# Sheet2.net
KiCad netlist of a schematic drawn in Altium Designer
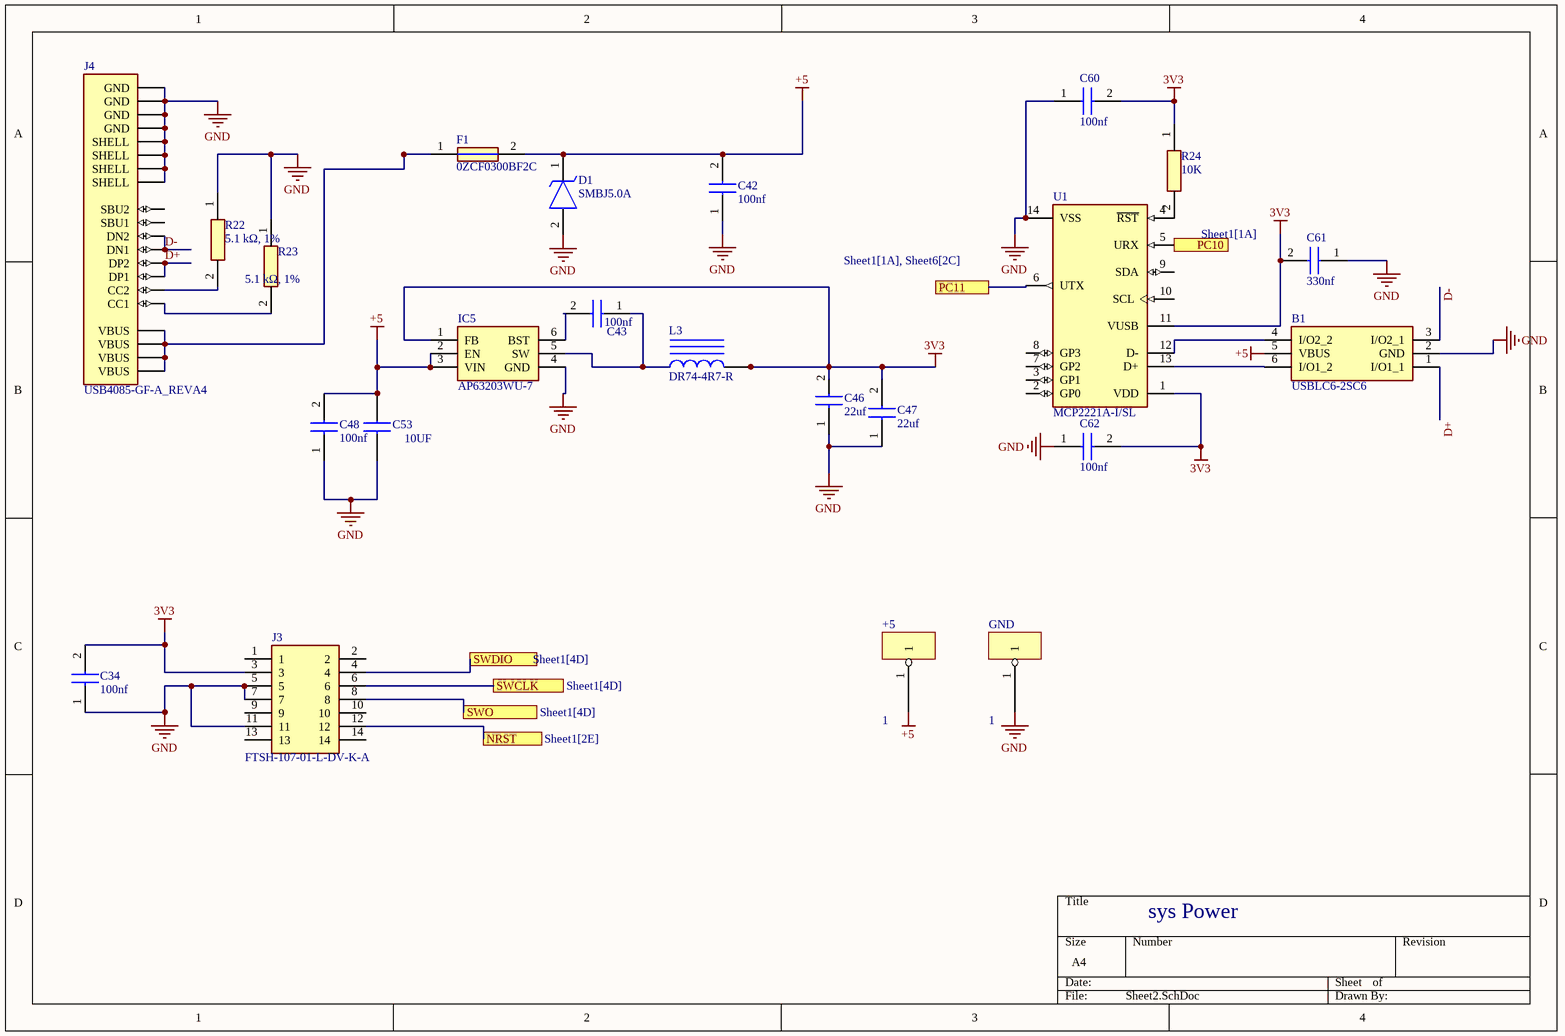
[diagram p0: Sheet2.SchDoc]

(export (version "E")
  (design (tool "Eeschema 10.0.6"))
  (components
    (comp (ref "+5") (value "1") (footprint "ANT") (libsource (lib "ANT") (part "1")))
    (comp (ref "B1")
      (value "USBLC6-2SC6")
      (footprint "SOT95P280X145-6N")
      (description "TVS Diode Array Uni-Directional USBLC6-2SC6 17V, SOT-23 6-Pin")
      (fields (field (name "MOUSER PART NUMBER") "511-USBLC6-2SC6"))
      (libsource (lib "USBLC6-2SC6") (part "USBLC6-2SC6"))
    )
    (comp (ref "C34")
      (value "100nf")
      (footprint "SamacSys:CAPC1608X95N")
      (description "Capacitor")
      (fields (field (name "MANUFACTURER_PART_NUMBER") "VJ0603Y104KXACW1BC"))
      (libsource (lib "*") (part "VJ0603Y104KXACW1BC"))
    )
    (comp (ref "C42")
      (value "100nf")
      (footprint "SamacSys:CAPC1608X95N")
      (description "Capacitor")
      (fields (field (name "MANUFACTURER_PART_NUMBER") "VJ0603Y104KXACW1BC"))
      (libsource (lib "*") (part "VJ0603Y104KXACW1BC"))
    )
    (comp (ref "C43")
      (value "100nf")
      (footprint "SamacSys:CAPC1608X95N")
      (description "Capacitor")
      (fields (field (name "MANUFACTURER_PART_NUMBER") "VJ0603Y104KXACW1BC"))
      (libsource (lib "*") (part "VJ0603Y104KXACW1BC"))
    )
    (comp (ref "C46")
      (value "22uf")
      (footprint "SamacSys:CAPC1608X95N")
      (description "Capacitor")
      (fields (field (name "MANUFACTURER_PART_NUMBER") "VJ0603Y104KXACW1BC"))
      (libsource (lib "*") (part "VJ0603Y104KXACW1BC"))
    )
    (comp (ref "C47")
      (value "22uf")
      (footprint "SamacSys:CAPC1608X95N")
      (description "Capacitor")
      (fields (field (name "MANUFACTURER_PART_NUMBER") "VJ0603Y104KXACW1BC"))
      (libsource (lib "*") (part "VJ0603Y104KXACW1BC"))
    )
    (comp (ref "C48")
      (value "100nf")
      (footprint "SamacSys:CAPC1608X95N")
      (description "Capacitor")
      (fields (field (name "MANUFACTURER_PART_NUMBER") "VJ0603Y104KXACW1BC"))
      (libsource (lib "*") (part "VJ0603Y104KXACW1BC"))
    )
    (comp (ref "C53")
      (value "10UF")
      (footprint "CAPC1608X90N")
      (description "10F +/-10% 10V Ceramic Capacitor X5R 0603 (1608 Metric)")
      (fields
        (field (name "MANUFACTURER_PART_NUMBER") "CL10A106KP8NNNC")
        (field (name "MOUSER PART NUMBER") "187-CL10A106KP8NNNC")
      )
      (libsource (lib "CL10A106KP8NNNC") (part "CL10A106KP8NNNC"))
    )
    (comp (ref "C60")
      (value "100nf")
      (footprint "SamacSys:CAPC1608X95N")
      (description "Capacitor")
      (fields (field (name "MANUFACTURER_PART_NUMBER") "VJ0603Y104KXACW1BC"))
      (libsource (lib "*") (part "VJ0603Y104KXACW1BC"))
    )
    (comp (ref "C61")
      (value "330nf")
      (footprint "SamacSys:CAPC1608X95N")
      (description "Capacitor")
      (fields (field (name "MANUFACTURER_PART_NUMBER") "VJ0603Y104KXACW1BC"))
      (libsource (lib "*") (part "VJ0603Y104KXACW1BC"))
    )
    (comp (ref "C62")
      (value "100nf")
      (footprint "SamacSys:CAPC1608X95N")
      (description "Capacitor")
      (fields (field (name "MANUFACTURER_PART_NUMBER") "VJ0603Y104KXACW1BC"))
      (libsource (lib "*") (part "VJ0603Y104KXACW1BC"))
    )
    (comp (ref "D1")
      (value "SMBJ5.0A")
      (footprint "SamacSys:SMBJ12A")
      (description "TVS Diode (Uni-directional)")
      (libsource (lib "SamacSys") (part "SMBJ5.0A"))
    )
    (comp (ref "F1")
      (value "0ZCF0300BF2C")
      (footprint "SamacSys:FUSC7451X115N")
      (description "Fuse")
      (fields (field (name "MOUSER PART NUMBER") "530-0ZCF0300BF2C"))
      (libsource (lib "*") (part "0ZCF0300BF2C"))
    )
    (comp (ref "GND") (value "1") (footprint "ANT") (libsource (lib "ANT") (part "1")))
    (comp (ref "IC5")
      (value "AP63203WU-7")
      (footprint "SamacSys:AP63203WU7")
      (description "Integrated Circuit")
      (fields (field (name "MOUSER PART NUMBER") "621-AP63203WU-7"))
      (libsource (lib "*") (part "AP63203WU-7"))
    )
    (comp (ref "J3")
      (value "FTSH-107-01-L-DV-K-A")
      (footprint "SamacSys:FTSH-107-XX-YYY-DV-K-A")
      (description "Connector")
      (fields (field (name "MOUSER PART NUMBER") "200-FTSH10701LDVKA"))
      (libsource (lib "*") (part "FTSH-107-01-L-DV-K-A"))
    )
    (comp (ref "J4")
      (value "USB4085-GF-A_REVA4")
      (footprint "GCT_USB4085-GF-A_REVA4")
      (fields (field (name "MP") "USB4085-GF-A") (field (name "MF") "Global Connector Technology"))
      (libsource (lib "USB4085-GF-A_REVA4") (part "USB4085-GF-A_REVA4"))
    )
    (comp (ref "L3")
      (value "DR74-4R7-R")
      (footprint "COBU-DR74-4R7-R_V")
      (fields (field (name "MANUFACTURER") "Eaton") (field (name "TOLERANCE") "±20%"))
      (libsource (lib "Altium Content Vault") (part "IND-DOT-2_A"))
    )
    (comp (ref "R22")
      (value "5.1 kΩ, 1%")
      (footprint "SamacSys:RESC1608X55N")
      (description "Resistor")
      (fields
        (field (name "MANUFACTURER_PART_NUMBER") "RC0603FR-071KL")
        (field (name "MOUSER PART NUMBER") "603-RC0603FR-071KL")
      )
      (libsource (lib "*") (part "RC0603FR-071KL"))
    )
    (comp (ref "R23")
      (value "5.1 kΩ, 1%")
      (footprint "SamacSys:RESC1608X55N")
      (description "Resistor")
      (fields
        (field (name "MANUFACTURER_PART_NUMBER") "RC0603FR-071KL")
        (field (name "MOUSER PART NUMBER") "603-RC0603FR-071KL")
      )
      (libsource (lib "*") (part "RC0603FR-071KL"))
    )
    (comp (ref "R24")
      (value "10K")
      (footprint "SamacSys:RESC1608X55N")
      (description "Resistor")
      (fields
        (field (name "MANUFACTURER_PART_NUMBER") "RC0603FR-071KL")
        (field (name "MOUSER PART NUMBER") "603-RC0603FR-071KL")
      )
      (libsource (lib "*") (part "RC0603FR-071KL"))
    )
    (comp (ref "U1")
      (value "MCP2221A-I/SL")
      (footprint "FP-C04-065-SL-MFG")
      (description "IC USB TO I2C/UART 14SOIC")
      (fields
        (field (name "OCTOPART") "https://octopart.com/mcp2221a-i%2Fsl-microchip-71704986")
        (field (name "MANUFACTURER") "Microchip")
      )
      (libsource (lib "Altium Content Vault") (part "1b53208594fde27bd45fc2fa1d78706"))
    )
  )
  (nets
    (net (code "1") (name "+5") (class "Default")
      (node (ref "+5") (pin "1") (pinfunction "1_1") (pintype "passive"))
      (node (ref "B1") (pin "5") (pinfunction "VBUS_5") (pintype "passive"))
      (node (ref "C42") (pin "2") (pinfunction "2_2") (pintype "passive"))
      (node (ref "C48") (pin "2") (pinfunction "2_2") (pintype "passive"))
      (node (ref "C53") (pin "2") (pinfunction "2_2") (pintype "passive"))
      (node (ref "D1") (pin "1") (pinfunction "K_1") (pintype "passive"))
      (node (ref "F1") (pin "2") (pinfunction "2_2") (pintype "passive"))
      (node (ref "IC5") (pin "2") (pinfunction "EN_2") (pintype "passive"))
      (node (ref "IC5") (pin "3") (pinfunction "VIN_3") (pintype "passive"))
    )
    (net (code "2") (name "/D+") (class "Default")
      (node (ref "B1") (pin "1") (pinfunction "I/O1_1_1") (pintype "passive"))
      (node (ref "J4") (pin "A6") (pinfunction "DP1_A6") (pintype "bidirectional"))
      (node (ref "J4") (pin "B6") (pinfunction "DP2_B6") (pintype "bidirectional"))
    )
    (net (code "3") (name "/D-") (class "Default")
      (node (ref "B1") (pin "3") (pinfunction "I/O2_1_3") (pintype "passive"))
      (node (ref "J4") (pin "A7") (pinfunction "DN1_A7") (pintype "bidirectional"))
      (node (ref "J4") (pin "B7") (pinfunction "DN2_B7") (pintype "bidirectional"))
    )
    (net (code "4") (name "/NRST") (class "Default")
      (node (ref "J3") (pin "12") (pinfunction "12_12") (pintype "passive"))
    )
    (net (code "5") (name "/PC10") (class "Default")
      (node (ref "U1") (pin "5") (pinfunction "URX_5") (pintype "input"))
    )
    (net (code "6") (name "/PC11") (class "Default")
      (node (ref "U1") (pin "6") (pinfunction "UTX_6") (pintype "output"))
    )
    (net (code "7") (name "/SWCLK") (class "Default")
      (node (ref "J3") (pin "6") (pinfunction "6_6") (pintype "passive"))
    )
    (net (code "8") (name "/SWDIO") (class "Default")
      (node (ref "J3") (pin "4") (pinfunction "4_4") (pintype "passive"))
    )
    (net (code "9") (name "/SWO") (class "Default")
      (node (ref "J3") (pin "8") (pinfunction "8_8") (pintype "passive"))
    )
    (net (code "10") (name "3V3") (class "Default")
      (node (ref "C34") (pin "2") (pinfunction "2_2") (pintype "passive"))
      (node (ref "C46") (pin "2") (pinfunction "2_2") (pintype "passive"))
      (node (ref "C47") (pin "2") (pinfunction "2_2") (pintype "passive"))
      (node (ref "C60") (pin "2") (pinfunction "2_2") (pintype "passive"))
      (node (ref "C61") (pin "2") (pinfunction "2_2") (pintype "passive"))
      (node (ref "C62") (pin "2") (pinfunction "2_2") (pintype "passive"))
      (node (ref "IC5") (pin "1") (pinfunction "FB_1") (pintype "passive"))
      (node (ref "J3") (pin "3") (pinfunction "3_3") (pintype "passive"))
      (node (ref "L3") (pin "2") (pinfunction "2_2") (pintype "passive"))
      (node (ref "R24") (pin "1") (pinfunction "1_1") (pintype "passive"))
      (node (ref "U1") (pin "1") (pinfunction "VDD_1") (pintype "power_in"))
      (node (ref "U1") (pin "11") (pinfunction "VUSB_11") (pintype "power_in"))
    )
    (net (code "11") (name "GND") (class "Default")
      (node (ref "B1") (pin "2") (pinfunction "GND_2") (pintype "passive"))
      (node (ref "C34") (pin "1") (pinfunction "1_1") (pintype "passive"))
      (node (ref "C42") (pin "1") (pinfunction "1_1") (pintype "passive"))
      (node (ref "C46") (pin "1") (pinfunction "1_1") (pintype "passive"))
      (node (ref "C47") (pin "1") (pinfunction "1_1") (pintype "passive"))
      (node (ref "C48") (pin "1") (pinfunction "1_1") (pintype "passive"))
      (node (ref "C53") (pin "1") (pinfunction "1_1") (pintype "passive"))
      (node (ref "C60") (pin "1") (pinfunction "1_1") (pintype "passive"))
      (node (ref "C61") (pin "1") (pinfunction "1_1") (pintype "passive"))
      (node (ref "C62") (pin "1") (pinfunction "1_1") (pintype "passive"))
      (node (ref "D1") (pin "2") (pinfunction "A_2") (pintype "passive"))
      (node (ref "GND") (pin "1") (pinfunction "1_1") (pintype "passive"))
      (node (ref "IC5") (pin "4") (pinfunction "GND_4") (pintype "passive"))
      (node (ref "J3") (pin "11") (pinfunction "11_11") (pintype "passive"))
      (node (ref "J3") (pin "5") (pinfunction "5_5") (pintype "passive"))
      (node (ref "J3") (pin "7") (pinfunction "7_7") (pintype "passive"))
      (node (ref "J4") (pin "A1") (pinfunction "GND_A1") (pintype "power_in"))
      (node (ref "J4") (pin "A12") (pinfunction "GND_A12") (pintype "power_in"))
      (node (ref "J4") (pin "B1") (pinfunction "GND_B1") (pintype "power_in"))
      (node (ref "J4") (pin "B12") (pinfunction "GND_B12") (pintype "power_in"))
      (node (ref "J4") (pin "S1") (pinfunction "SHELL_S1") (pintype "passive"))
      (node (ref "J4") (pin "S2") (pinfunction "SHELL_S2") (pintype "passive"))
      (node (ref "J4") (pin "S3") (pinfunction "SHELL_S3") (pintype "passive"))
      (node (ref "J4") (pin "S4") (pinfunction "SHELL_S4") (pintype "passive"))
      (node (ref "R22") (pin "1") (pinfunction "1_1") (pintype "passive"))
      (node (ref "R23") (pin "1") (pinfunction "1_1") (pintype "passive"))
      (node (ref "U1") (pin "14") (pinfunction "VSS_14") (pintype "power_in"))
    )
    (net (code "12") (name "Net-(B1-I{slash}O1_2)") (class "Default")
      (node (ref "B1") (pin "6") (pinfunction "I/O1_2_6") (pintype "passive"))
      (node (ref "U1") (pin "13") (pinfunction "D+_13") (pintype "power_in"))
    )
    (net (code "13") (name "Net-(B1-I{slash}O2_2)") (class "Default")
      (node (ref "B1") (pin "4") (pinfunction "I/O2_2_4") (pintype "passive"))
      (node (ref "U1") (pin "12") (pinfunction "D-_12") (pintype "power_in"))
    )
    (net (code "14") (name "Net-(F1-Pad1)") (class "Default")
      (node (ref "F1") (pin "1") (pinfunction "1_1") (pintype "passive"))
      (node (ref "J4") (pin "A4") (pinfunction "VBUS_A4") (pintype "power_in"))
      (node (ref "J4") (pin "A9") (pinfunction "VBUS_A9") (pintype "power_in"))
      (node (ref "J4") (pin "B4") (pinfunction "VBUS_B4") (pintype "power_in"))
      (node (ref "J4") (pin "B9") (pinfunction "VBUS_B9") (pintype "power_in"))
    )
    (net (code "15") (name "Net-(IC5-BST)") (class "Default")
      (node (ref "C43") (pin "2") (pinfunction "2_2") (pintype "passive"))
      (node (ref "IC5") (pin "6") (pinfunction "BST_6") (pintype "passive"))
    )
    (net (code "16") (name "Net-(IC5-SW)") (class "Default")
      (node (ref "C43") (pin "1") (pinfunction "1_1") (pintype "passive"))
      (node (ref "IC5") (pin "5") (pinfunction "SW_5") (pintype "passive"))
      (node (ref "L3") (pin "1") (pinfunction "1_1") (pintype "passive"))
    )
    (net (code "17") (name "Net-(J4-CC1)") (class "Default")
      (node (ref "J4") (pin "A5") (pinfunction "CC1_A5") (pintype "bidirectional"))
      (node (ref "R23") (pin "2") (pinfunction "2_2") (pintype "passive"))
    )
    (net (code "18") (name "Net-(J4-CC2)") (class "Default")
      (node (ref "J4") (pin "B5") (pinfunction "CC2_B5") (pintype "bidirectional"))
      (node (ref "R22") (pin "2") (pinfunction "2_2") (pintype "passive"))
    )
    (net (code "19") (name "Net-(U1-~{RST})") (class "Default")
      (node (ref "R24") (pin "2") (pinfunction "2_2") (pintype "passive"))
      (node (ref "U1") (pin "4") (pinfunction "~{RST}_4") (pintype "input"))
    )
    (net (code "20") (name "unconnected-(J3-Pad1)") (class "Default")
      (node (ref "J3") (pin "1") (pinfunction "1_1") (pintype "passive"))
    )
    (net (code "21") (name "unconnected-(J3-Pad2)") (class "Default")
      (node (ref "J3") (pin "2") (pinfunction "2_2") (pintype "passive"))
    )
    (net (code "22") (name "unconnected-(J3-Pad9)") (class "Default")
      (node (ref "J3") (pin "9") (pinfunction "9_9") (pintype "passive"))
    )
    (net (code "23") (name "unconnected-(J3-Pad10)") (class "Default")
      (node (ref "J3") (pin "10") (pinfunction "10_10") (pintype "passive"))
    )
    (net (code "24") (name "unconnected-(J3-Pad13)") (class "Default")
      (node (ref "J3") (pin "13") (pinfunction "13_13") (pintype "passive"))
    )
    (net (code "25") (name "unconnected-(J3-Pad14)") (class "Default")
      (node (ref "J3") (pin "14") (pinfunction "14_14") (pintype "passive"))
    )
    (net (code "26") (name "unconnected-(J4-SBU1-PadA8)") (class "Default")
      (node (ref "J4") (pin "A8") (pinfunction "SBU1_A8") (pintype "bidirectional"))
    )
    (net (code "27") (name "unconnected-(J4-SBU2-PadB8)") (class "Default")
      (node (ref "J4") (pin "B8") (pinfunction "SBU2_B8") (pintype "bidirectional"))
    )
    (net (code "28") (name "unconnected-(U1-GP0-Pad2)") (class "Default")
      (node (ref "U1") (pin "2") (pinfunction "GP0_2") (pintype "bidirectional"))
    )
    (net (code "29") (name "unconnected-(U1-GP1-Pad3)") (class "Default")
      (node (ref "U1") (pin "3") (pinfunction "GP1_3") (pintype "bidirectional"))
    )
    (net (code "30") (name "unconnected-(U1-GP2-Pad7)") (class "Default")
      (node (ref "U1") (pin "7") (pinfunction "GP2_7") (pintype "bidirectional"))
    )
    (net (code "31") (name "unconnected-(U1-GP3-Pad8)") (class "Default")
      (node (ref "U1") (pin "8") (pinfunction "GP3_8") (pintype "bidirectional"))
    )
    (net (code "32") (name "unconnected-(U1-SCL-Pad10)") (class "Default")
      (node (ref "U1") (pin "10") (pinfunction "SCL_10") (pintype "input"))
    )
    (net (code "33") (name "unconnected-(U1-SDA-Pad9)") (class "Default")
      (node (ref "U1") (pin "9") (pinfunction "SDA_9") (pintype "bidirectional"))
    )
  )
)
